# Comparator_circuit.net
KiCad netlist of a schematic drawn in Altium Designer
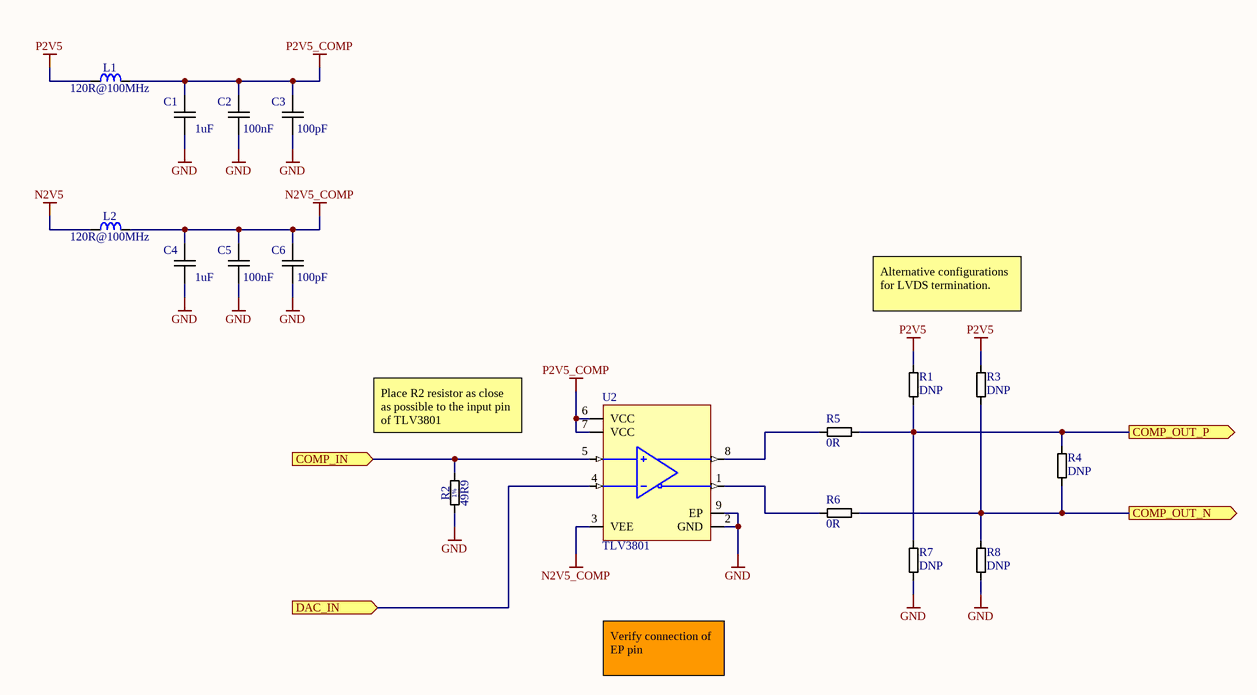
[diagram p0: Comparator_circuit.SchDoc]

(export (version "E")
  (design (tool "Eeschema 10.0.6"))
  (components
    (comp (ref "C1")
      (value "1uF")
      (footprint "CAPC0603X90N")
      (description "Non-polarised capacitor")
      (fields (field (name "MANUFACTURER PART NUMBER") "CL10B105KO8NNNC"))
      (libsource (lib "Capacitors") (part "Capacitor - non polarized"))
    )
    (comp (ref "C2")
      (value "100nF")
      (footprint "CAPC0603X90N")
      (description "Non-polarised capacitor")
      (fields (field (name "MANUFACTURER PART NUMBER") "VJ0603Y104KXJCW1BC"))
      (libsource (lib "Capacitors") (part "Capacitor - non polarized"))
    )
    (comp (ref "C3")
      (value "100pF")
      (footprint "CAPC0603X90N")
      (description "Non-polarised capacitor")
      (fields (field (name "MANUFACTURER PART NUMBER") "06035C101JAT2A"))
      (libsource (lib "Capacitors") (part "Capacitor - non polarized"))
    )
    (comp (ref "C4")
      (value "1uF")
      (footprint "CAPC0603X90N")
      (description "Non-polarised capacitor")
      (fields (field (name "MANUFACTURER PART NUMBER") "CL10B105KO8NNNC"))
      (libsource (lib "Capacitors") (part "Capacitor - non polarized"))
    )
    (comp (ref "C5")
      (value "100nF")
      (footprint "CAPC0603X90N")
      (description "Non-polarised capacitor")
      (fields (field (name "MANUFACTURER PART NUMBER") "VJ0603Y104KXJCW1BC"))
      (libsource (lib "Capacitors") (part "Capacitor - non polarized"))
    )
    (comp (ref "C6")
      (value "100pF")
      (footprint "CAPC0603X90N")
      (description "Non-polarised capacitor")
      (fields (field (name "MANUFACTURER PART NUMBER") "06035C101JAT2A"))
      (libsource (lib "Capacitors") (part "Capacitor - non polarized"))
    )
    (comp (ref "L1")
      (value "120R@100MHz")
      (footprint "INDC0603X90N")
      (description "Ferrite Bead")
      (fields (field (name "MANUFACTURER PART NUMBER") "BLM18PG121SN1D") (field (name "TOLERANCE") "25%"))
      (libsource (lib "Inductors") (part "Inductor"))
    )
    (comp (ref "L2")
      (value "120R@100MHz")
      (footprint "INDC0603X90N")
      (description "Ferrite Bead")
      (fields (field (name "MANUFACTURER PART NUMBER") "BLM18PG121SN1D") (field (name "TOLERANCE") "25%"))
      (libsource (lib "Inductors") (part "Inductor"))
    )
    (comp (ref "R1")
      (value "DNP")
      (footprint "RESC0402X40N")
      (description "General Purpose Thick Film Chip Resistor")
      (fields (field (name "VOLTAGE") "50V"))
      (libsource (lib "Resistors") (part "Resistor - Generic"))
    )
    (comp (ref "R2")
      (value "49R9")
      (footprint "RESC0402X40N")
      (description "General Purpose Thick Film Chip Resistor")
      (fields (field (name "MANUFACTURER PART NUMBER") "RC0402FR-0749R9L") (field (name "TOLERANCE") "1%"))
      (libsource (lib "Resistors") (part "Resistor - 1%"))
    )
    (comp (ref "R3")
      (value "DNP")
      (footprint "RESC0402X40N")
      (description "General Purpose Thick Film Chip Resistor")
      (fields (field (name "VOLTAGE") "50V"))
      (libsource (lib "Resistors") (part "Resistor - Generic"))
    )
    (comp (ref "R4")
      (value "DNP")
      (footprint "RESC0402X40N")
      (description "General Purpose Thick Film Chip Resistor")
      (fields (field (name "VOLTAGE") "50V"))
      (libsource (lib "Resistors") (part "Resistor - Generic"))
    )
    (comp (ref "R5")
      (value "0R")
      (footprint "RESC0402X40N")
      (description "General Purpose Thick Film Chip Resistor")
      (fields
        (field (name "MANUFACTURER PART NUMBER") "CRCW04020000Z0EDC")
        (field (name "TOLERANCE") "20mOhm")
      )
      (libsource (lib "Resistors") (part "Resistor - Generic"))
    )
    (comp (ref "R6")
      (value "0R")
      (footprint "RESC0402X40N")
      (description "General Purpose Thick Film Chip Resistor")
      (fields
        (field (name "MANUFACTURER PART NUMBER") "CRCW04020000Z0EDC")
        (field (name "TOLERANCE") "20mOhm")
      )
      (libsource (lib "Resistors") (part "Resistor - Generic"))
    )
    (comp (ref "R7")
      (value "DNP")
      (footprint "RESC0402X40N")
      (description "General Purpose Thick Film Chip Resistor")
      (fields (field (name "VOLTAGE") "50V"))
      (libsource (lib "Resistors") (part "Resistor - Generic"))
    )
    (comp (ref "R8")
      (value "DNP")
      (footprint "RESC0402X40N")
      (description "General Purpose Thick Film Chip Resistor")
      (fields (field (name "VOLTAGE") "50V"))
      (libsource (lib "Resistors") (part "Resistor - Generic"))
    )
    (comp (ref "U2")
      (value "TLV3801")
      (description "225-ps High-Speed Comparator with LVDS Outputs")
      (fields (field (name "MANUFACTURER PART NUMBER") "TLV3801DSG(_)"))
      (libsource (lib "ICs_and_Semiconductors") (part "TLV3801"))
    )
  )
  (nets
    (net (code "1") (name "/COMP_IN") (class "Default")
      (node (ref "R2") (pin "2") (pinfunction "2_2") (pintype "passive"))
      (node (ref "U2") (pin "5") (pinfunction "IN+_5") (pintype "input"))
    )
    (net (code "2") (name "/COMP_OUT_N") (class "Default")
      (node (ref "R3") (pin "1") (pinfunction "1_1") (pintype "passive"))
      (node (ref "R4") (pin "1") (pinfunction "1_1") (pintype "passive"))
      (node (ref "R6") (pin "2") (pinfunction "2_2") (pintype "passive"))
      (node (ref "R8") (pin "2") (pinfunction "2_2") (pintype "passive"))
    )
    (net (code "3") (name "/COMP_OUT_P") (class "Default")
      (node (ref "R1") (pin "1") (pinfunction "1_1") (pintype "passive"))
      (node (ref "R4") (pin "2") (pinfunction "2_2") (pintype "passive"))
      (node (ref "R5") (pin "2") (pinfunction "2_2") (pintype "passive"))
      (node (ref "R7") (pin "2") (pinfunction "2_2") (pintype "passive"))
    )
    (net (code "4") (name "/DAC_IN") (class "Default")
      (node (ref "U2") (pin "4") (pinfunction "IN-_4") (pintype "input"))
    )
    (net (code "5") (name "GND") (class "Default")
      (node (ref "C1") (pin "2") (pinfunction "2_2") (pintype "passive"))
      (node (ref "C2") (pin "2") (pinfunction "2_2") (pintype "passive"))
      (node (ref "C3") (pin "2") (pinfunction "2_2") (pintype "passive"))
      (node (ref "C4") (pin "2") (pinfunction "2_2") (pintype "passive"))
      (node (ref "C5") (pin "2") (pinfunction "2_2") (pintype "passive"))
      (node (ref "C6") (pin "2") (pinfunction "2_2") (pintype "passive"))
      (node (ref "R2") (pin "1") (pinfunction "1_1") (pintype "passive"))
      (node (ref "R7") (pin "1") (pinfunction "1_1") (pintype "passive"))
      (node (ref "R8") (pin "1") (pinfunction "1_1") (pintype "passive"))
      (node (ref "U2") (pin "2") (pinfunction "GND_2") (pintype "power_in"))
      (node (ref "U2") (pin "9") (pinfunction "EP_9") (pintype "power_in"))
    )
    (net (code "6") (name "N2V5") (class "Default")
      (node (ref "L2") (pin "1") (pinfunction "1_1") (pintype "passive"))
    )
    (net (code "7") (name "N2V5_COMP") (class "Default")
      (node (ref "C4") (pin "1") (pinfunction "1_1") (pintype "passive"))
      (node (ref "C5") (pin "1") (pinfunction "1_1") (pintype "passive"))
      (node (ref "C6") (pin "1") (pinfunction "1_1") (pintype "passive"))
      (node (ref "L2") (pin "2") (pinfunction "2_2") (pintype "passive"))
      (node (ref "U2") (pin "3") (pinfunction "VEE_3") (pintype "power_in"))
    )
    (net (code "8") (name "Net-(U2-OUT+)") (class "Default")
      (node (ref "R5") (pin "1") (pinfunction "1_1") (pintype "passive"))
      (node (ref "U2") (pin "8") (pinfunction "OUT+_8") (pintype "output"))
    )
    (net (code "9") (name "Net-(U2-OUT-)") (class "Default")
      (node (ref "R6") (pin "1") (pinfunction "1_1") (pintype "passive"))
      (node (ref "U2") (pin "1") (pinfunction "OUT-_1") (pintype "output"))
    )
    (net (code "10") (name "P2V5") (class "Default")
      (node (ref "L1") (pin "1") (pinfunction "1_1") (pintype "passive"))
      (node (ref "R1") (pin "2") (pinfunction "2_2") (pintype "passive"))
      (node (ref "R3") (pin "2") (pinfunction "2_2") (pintype "passive"))
    )
    (net (code "11") (name "P2V5_COMP") (class "Default")
      (node (ref "C1") (pin "1") (pinfunction "1_1") (pintype "passive"))
      (node (ref "C2") (pin "1") (pinfunction "1_1") (pintype "passive"))
      (node (ref "C3") (pin "1") (pinfunction "1_1") (pintype "passive"))
      (node (ref "L1") (pin "2") (pinfunction "2_2") (pintype "passive"))
      (node (ref "U2") (pin "6") (pinfunction "VCC_6") (pintype "power_in"))
      (node (ref "U2") (pin "7") (pinfunction "VCC_7") (pintype "power_in"))
    )
  )
)
